# Main_PCB.net
KiCad netlist of a schematic drawn in Altium Designer
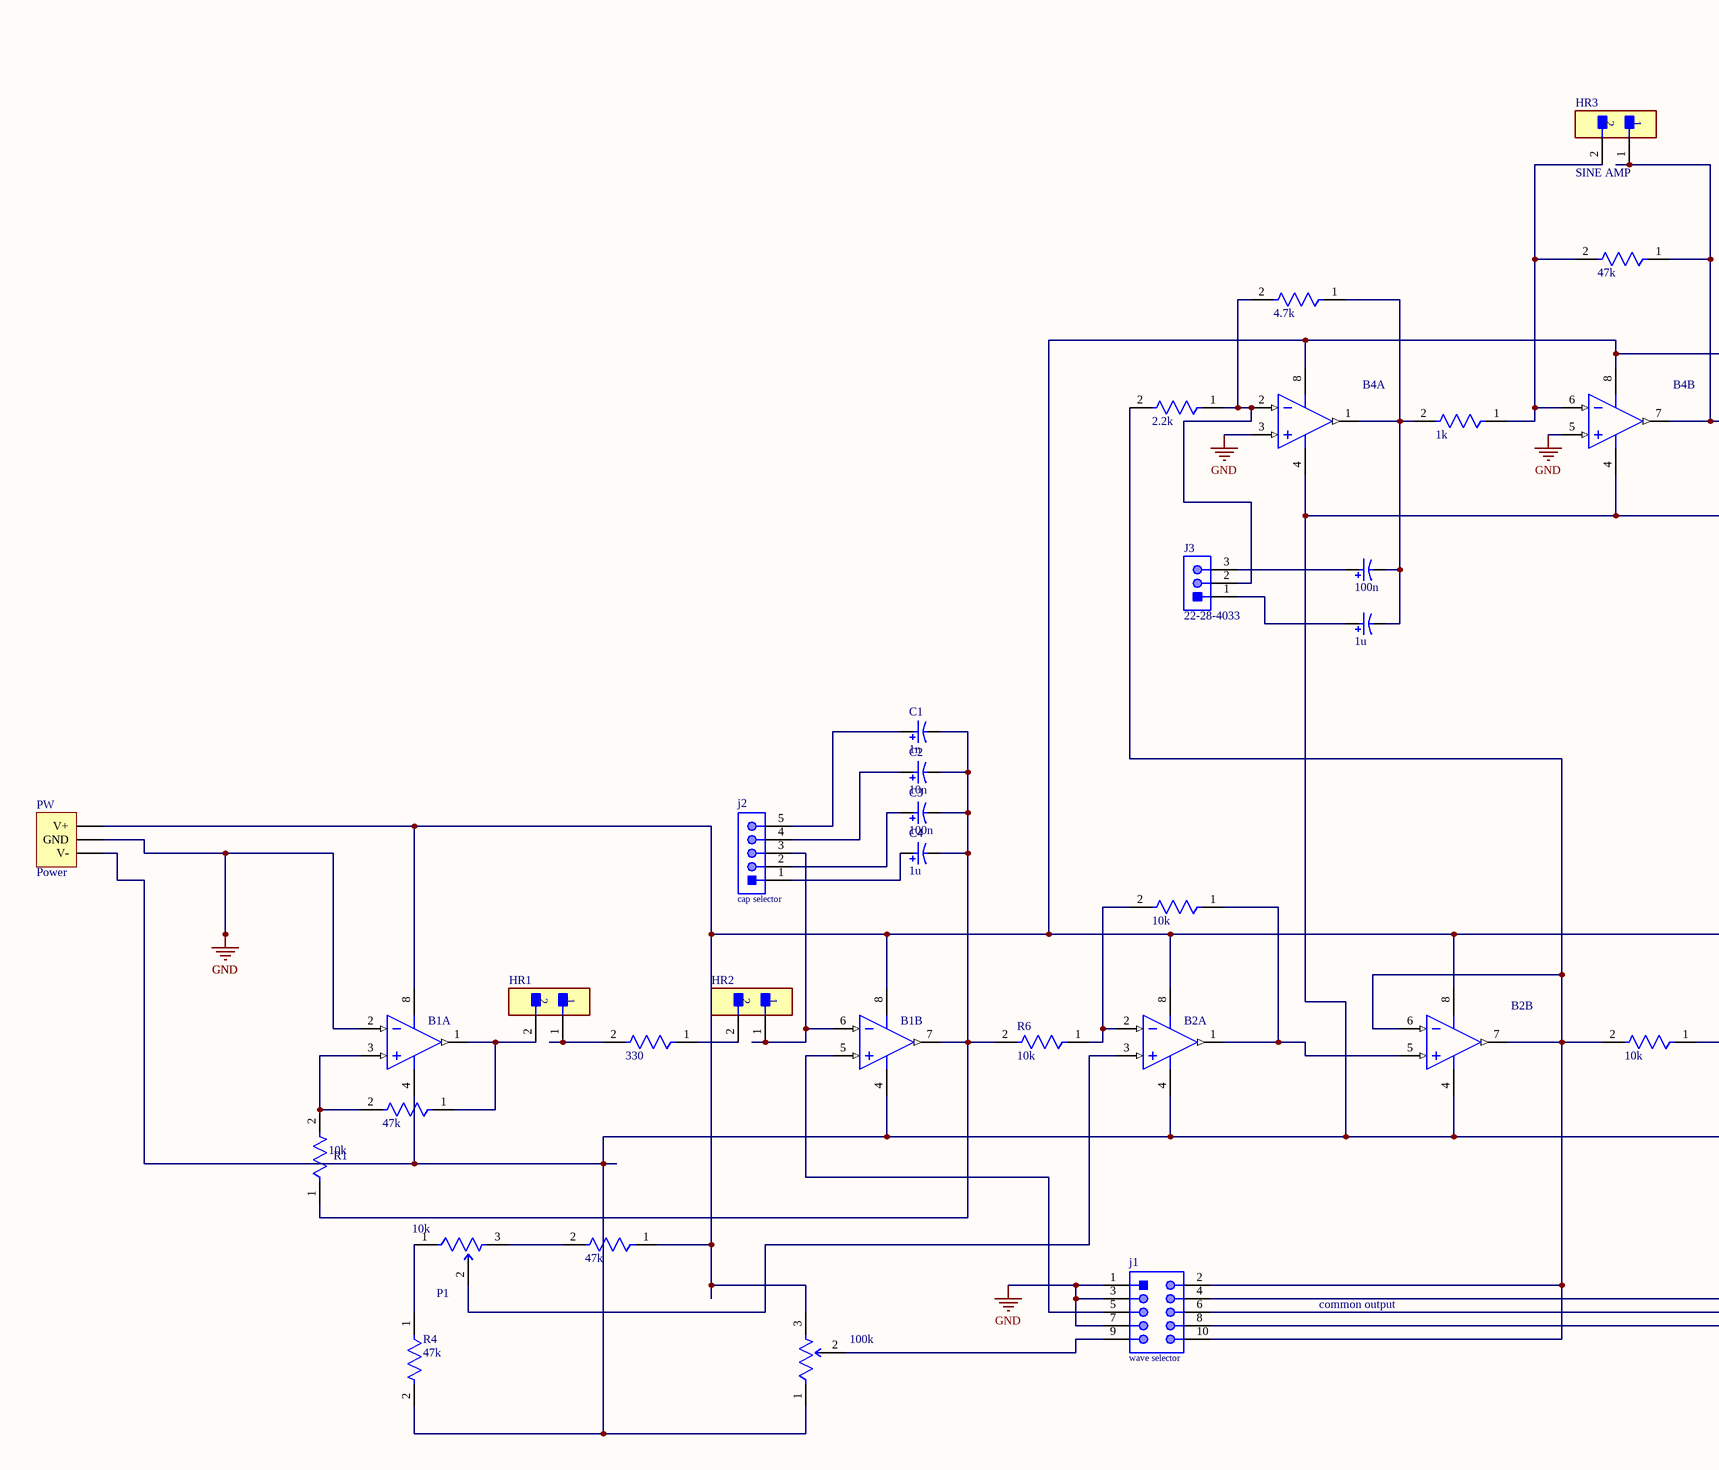
[diagram p0: Main_PCB.SchDoc, left]
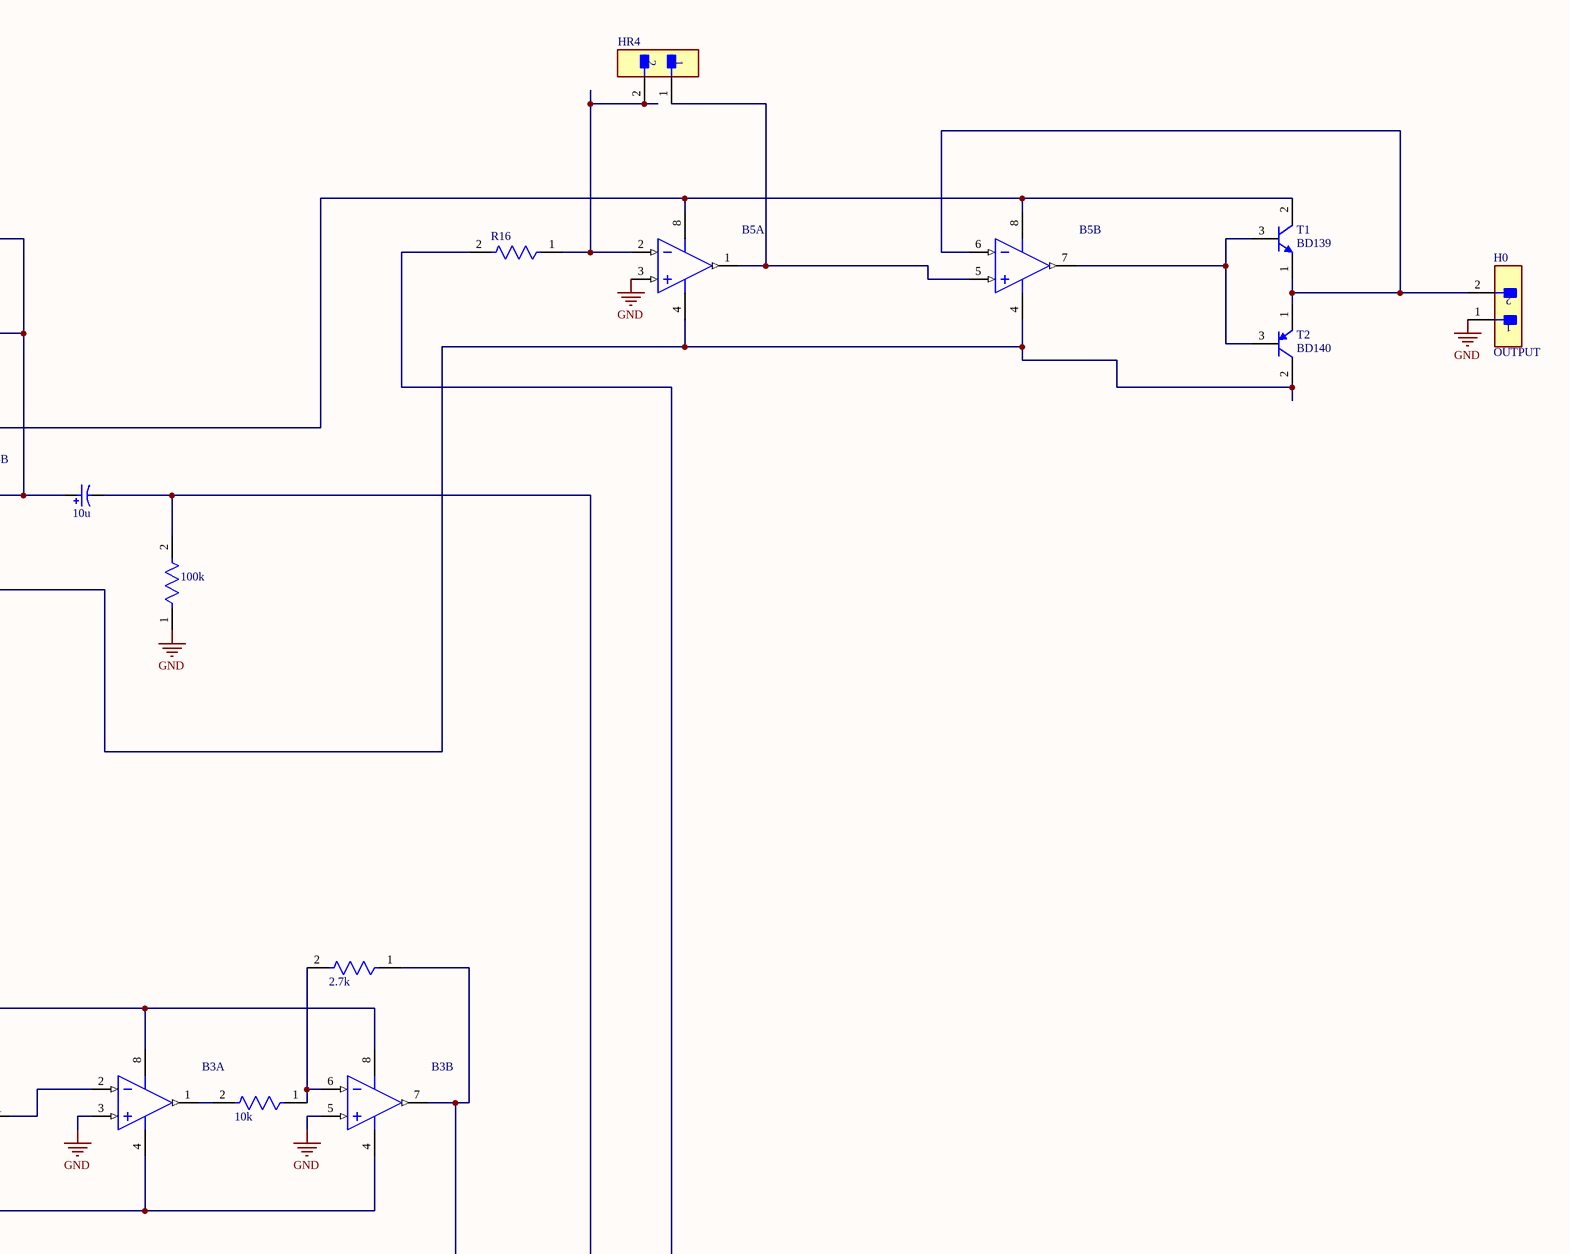
[diagram p1: Main_PCB.SchDoc, right]

(export (version "E")
  (design (tool "Eeschema 10.0.6"))
  (components
    (comp (ref "B1")
      (value "integrator")
      (footprint "ADI-N-8")
      (fields
        (field (name "MANUFACTURER") "Analog Devices")
        (field (name "PARTNUMBER") "AD826ANZ")
        (field (name "GENERIC PART NUMBER") "AD826")
      )
      (libsource (lib "Altium Content Vault") (part "ADI-AD7xx_8xx-X-8"))
    )
    (comp (ref "B2")
      (value "comparator gain")
      (footprint "ADI-N-8")
      (fields
        (field (name "MANUFACTURER") "Analog Devices")
        (field (name "PARTNUMBER") "AD826ANZ")
        (field (name "GENERIC PART NUMBER") "AD826")
      )
      (libsource (lib "Altium Content Vault") (part "ADI-AD7xx_8xx-X-8"))
    )
    (comp (ref "B3")
      (value "AD826ANZ")
      (footprint "ADI-N-8")
      (fields (field (name "MANUFACTURER") "Analog Devices") (field (name "GENERIC PART NUMBER") "AD826"))
      (libsource (lib "Altium Content Vault") (part "ADI-AD7xx_8xx-X-8"))
    )
    (comp (ref "B4")
      (value "AD826ANZ")
      (footprint "ADI-N-8")
      (fields (field (name "MANUFACTURER") "Analog Devices") (field (name "GENERIC PART NUMBER") "AD826"))
      (libsource (lib "Altium Content Vault") (part "ADI-AD7xx_8xx-X-8"))
    )
    (comp (ref "B5")
      (value "AD826ANZ")
      (footprint "ADI-N-8")
      (fields (field (name "MANUFACTURER") "Analog Devices") (field (name "GENERIC PART NUMBER") "AD826"))
      (libsource (lib "Altium Content Vault") (part "ADI-AD7xx_8xx-X-8"))
    )
    (comp (ref "C1")
      (value "1n")
      (footprint "CAPPR55-250-1120X630X1220")
      (fields (field (name "MANUFACTURER") "Panasonic"))
      (libsource (lib "Altium Content Vault") (part "CAP-P-2"))
    )
    (comp (ref "C2")
      (value "10n")
      (footprint "CAPPR55-250-1120X630X1220")
      (fields (field (name "MANUFACTURER") "Panasonic"))
      (libsource (lib "Altium Content Vault") (part "CAP-P-2"))
    )
    (comp (ref "C3")
      (value "100n")
      (footprint "CAPPR55-250-1120X630X1220")
      (fields (field (name "MANUFACTURER") "Panasonic"))
      (libsource (lib "Altium Content Vault") (part "CAP-P-2"))
    )
    (comp (ref "C4")
      (value "1u")
      (footprint "CAPPR55-250-1120X630X1220")
      (fields (field (name "MANUFACTURER") "Panasonic"))
      (libsource (lib "Altium Content Vault") (part "CAP-P-2"))
    )
    (comp (ref "C5")
      (value "100n")
      (footprint "CAPPR55-250-1120X630X1220")
      (fields (field (name "MANUFACTURER") "Panasonic"))
      (libsource (lib "Altium Content Vault") (part "CAP-P-2"))
    )
    (comp (ref "C6")
      (value "1u")
      (footprint "CAPPR55-250-1120X630X1220")
      (fields (field (name "MANUFACTURER") "Panasonic"))
      (libsource (lib "Altium Content Vault") (part "CAP-P-2"))
    )
    (comp (ref "C7")
      (value "10u")
      (footprint "CAPPR55-250-1120X630X1220")
      (fields (field (name "MANUFACTURER") "Panasonic"))
      (libsource (lib "Altium Content Vault") (part "CAP-P-2"))
    )
    (comp (ref "H0")
      (value "OUTPUT")
      (footprint "FP-TSW-102-07-L-S-MFG")
      (description "CONN HEADER VERT 2POS 2.54MM")
      (libsource (lib "") (part "3bc925449376181038e59eaffc5286c_1"))
    )
    (comp (ref "HR1")
      (value "FREQ")
      (footprint "FP-TSW-102-07-L-S-MFG")
      (description "CONN HEADER VERT 2POS 2.54MM")
      (libsource (lib "Altium Content Vault") (part "3bc925449376181038e59eaffc5286c"))
    )
    (comp (ref "HR2")
      (value "FREQ")
      (footprint "FP-TSW-102-07-L-S-MFG")
      (description "CONN HEADER VERT 2POS 2.54MM")
      (libsource (lib "Altium Content Vault") (part "3bc925449376181038e59eaffc5286c"))
    )
    (comp (ref "HR3")
      (value "SINE AMP")
      (footprint "FP-TSW-102-07-L-S-MFG")
      (description "CONN HEADER VERT 2POS 2.54MM")
      (libsource (lib "Altium Content Vault") (part "3bc925449376181038e59eaffc5286c"))
    )
    (comp (ref "HR4")
      (value "AMP")
      (footprint "FP-TSW-102-07-L-S-MFG")
      (description "CONN HEADER VERT 2POS 2.54MM")
      (libsource (lib "Altium Content Vault") (part "3bc925449376181038e59eaffc5286c"))
    )
    (comp (ref "j1")
      (value "wave selector")
      (footprint "61301021121")
      (description "THT Vertical Pin Header WR-PHD, Pitch 2.54 mm, Dual Row, 10 pins")
      (fields
        (field (name "MANUFACTURER") "Wurth Elektronik")
        (field (name "PART NUMBER") "61301021121")
        (field (name "PUBLISHER") "WurthElektronik")
      )
      (libsource (lib "Altium Content Vault") (part "WE-CN-2P-M-R10"))
    )
    (comp (ref "j2")
      (value "cap selector")
      (footprint "61300511121")
      (description "THT Vertical Pin Header WR-PHD, Pitch 2.54 mm, Single Row, 5 pins")
      (fields
        (field (name "PART NUMBER") "61300511121")
        (field (name "MANUFACTURER") "Wurth Elektronik")
        (field (name "PUBLISHER") "WurthElektronik")
      )
      (libsource (lib "Altium Content Vault") (part "WE-CN-1P-M-R5"))
    )
    (comp (ref "J3")
      (value "22-28-4033")
      (footprint "MOLX-22-28-4033_V")
      (description "Male Header, Pitch 2.54 mm, 1 x 3 Position, Height 8.38 mm, Tail Length 3.18 mm, RoHS, Bulk")
      (fields (field (name "MANUFACTURER") "Molex"))
      (libsource (lib "Altium Content Vault") (part "CN-1P-M-R3"))
    )
    (comp (ref "P1")
      (value "10k")
      (footprint "FP-3362P-1-503TLF-MFG")
      (description "TRIMMER 50K OHM 0.5W PC PIN TOP")
      (fields (field (name "TOLERANCE") "10%"))
      (libsource (lib "Altium Content Vault") (part "2dcfd2547301a7d3209a5e99acfd772"))
    )
    (comp (ref "P2")
      (value "100k")
      (footprint "FP-3362P-1-503TLF-MFG")
      (description "TRIMMER 50K OHM 0.5W PC PIN TOP")
      (fields (field (name "TOLERANCE") "10%"))
      (libsource (lib "Altium Content Vault") (part "2dcfd2547301a7d3209a5e99acfd772"))
    )
    (comp (ref "PW")
      (value "Power")
      (footprint "HDR1X3")
      (description "Header, 3-Pin")
      (fields (field (name "PUBLISHER") "Altium Limited"))
      (libsource (lib "Miscellaneous Connectors") (part "Header 3"))
    )
    (comp (ref "R1")
      (value "10k")
      (footprint "FP-CF18-MFG")
      (description "RES 10K OHM 1/8W 5% CF AXIAL")
      (fields
        (field (name "MANUFACTURER PART NUMBER") "CF18JT10K0")
        (field (name "MANUFACTURER") "Stackpole Electronics")
      )
      (libsource (lib "Altium Content Vault") (part "1029c3af85768c4190bb7ad29bc67b5"))
    )
    (comp (ref "R2")
      (value "47k")
      (footprint "FP-CF18-MFG")
      (description "RES 10K OHM 1/8W 5% CF AXIAL")
      (fields
        (field (name "MANUFACTURER PART NUMBER") "CF18JT10K0")
        (field (name "MANUFACTURER") "Stackpole Electronics")
      )
      (libsource (lib "Altium Content Vault") (part "1029c3af85768c4190bb7ad29bc67b5"))
    )
    (comp (ref "R3")
      (value "330")
      (footprint "FP-CF18-MFG")
      (description "RES 10K OHM 1/8W 5% CF AXIAL")
      (fields
        (field (name "MANUFACTURER PART NUMBER") "CF18JT10K0")
        (field (name "MANUFACTURER") "Stackpole Electronics")
      )
      (libsource (lib "Altium Content Vault") (part "1029c3af85768c4190bb7ad29bc67b5"))
    )
    (comp (ref "R4")
      (value "47k")
      (footprint "FP-CF18-MFG")
      (description "RES 10K OHM 1/8W 5% CF AXIAL")
      (fields
        (field (name "MANUFACTURER PART NUMBER") "CF18JT10K0")
        (field (name "MANUFACTURER") "Stackpole Electronics")
      )
      (libsource (lib "Altium Content Vault") (part "1029c3af85768c4190bb7ad29bc67b5"))
    )
    (comp (ref "R5")
      (value "47k")
      (footprint "FP-CF18-MFG")
      (description "RES 10K OHM 1/8W 5% CF AXIAL")
      (fields
        (field (name "MANUFACTURER PART NUMBER") "CF18JT10K0")
        (field (name "MANUFACTURER") "Stackpole Electronics")
      )
      (libsource (lib "Altium Content Vault") (part "1029c3af85768c4190bb7ad29bc67b5"))
    )
    (comp (ref "R6")
      (value "10k")
      (footprint "FP-CF18-MFG")
      (description "RES 10K OHM 1/8W 5% CF AXIAL")
      (fields
        (field (name "MANUFACTURER PART NUMBER") "CF18JT10K0")
        (field (name "MANUFACTURER") "Stackpole Electronics")
      )
      (libsource (lib "Altium Content Vault") (part "1029c3af85768c4190bb7ad29bc67b5"))
    )
    (comp (ref "R7")
      (value "10k")
      (footprint "FP-CF18-MFG")
      (description "RES 10K OHM 1/8W 5% CF AXIAL")
      (fields
        (field (name "MANUFACTURER PART NUMBER") "CF18JT10K0")
        (field (name "MANUFACTURER") "Stackpole Electronics")
      )
      (libsource (lib "Altium Content Vault") (part "1029c3af85768c4190bb7ad29bc67b5"))
    )
    (comp (ref "R8")
      (value "10k")
      (footprint "FP-CF18-MFG")
      (description "RES 10K OHM 1/8W 5% CF AXIAL")
      (fields
        (field (name "MANUFACTURER PART NUMBER") "CF18JT10K0")
        (field (name "MANUFACTURER") "Stackpole Electronics")
      )
      (libsource (lib "Altium Content Vault") (part "1029c3af85768c4190bb7ad29bc67b5"))
    )
    (comp (ref "R9")
      (value "10k")
      (footprint "FP-CF18-MFG")
      (description "RES 10K OHM 1/8W 5% CF AXIAL")
      (fields
        (field (name "MANUFACTURER PART NUMBER") "CF18JT10K0")
        (field (name "MANUFACTURER") "Stackpole Electronics")
      )
      (libsource (lib "Altium Content Vault") (part "1029c3af85768c4190bb7ad29bc67b5"))
    )
    (comp (ref "R10")
      (value "2.7k")
      (footprint "FP-CF18-MFG")
      (description "RES 10K OHM 1/8W 5% CF AXIAL")
      (fields
        (field (name "MANUFACTURER PART NUMBER") "CF18JT10K0")
        (field (name "MANUFACTURER") "Stackpole Electronics")
      )
      (libsource (lib "Altium Content Vault") (part "1029c3af85768c4190bb7ad29bc67b5"))
    )
    (comp (ref "R11")
      (value "2.2k")
      (footprint "FP-CF18-MFG")
      (description "RES 10K OHM 1/8W 5% CF AXIAL")
      (fields
        (field (name "MANUFACTURER PART NUMBER") "CF18JT10K0")
        (field (name "MANUFACTURER") "Stackpole Electronics")
      )
      (libsource (lib "Altium Content Vault") (part "1029c3af85768c4190bb7ad29bc67b5"))
    )
    (comp (ref "R12")
      (value "4.7k")
      (footprint "FP-CF18-MFG")
      (description "RES 10K OHM 1/8W 5% CF AXIAL")
      (fields
        (field (name "MANUFACTURER PART NUMBER") "CF18JT10K0")
        (field (name "MANUFACTURER") "Stackpole Electronics")
      )
      (libsource (lib "Altium Content Vault") (part "1029c3af85768c4190bb7ad29bc67b5"))
    )
    (comp (ref "R13")
      (value "1k")
      (footprint "FP-CF18-MFG")
      (description "RES 10K OHM 1/8W 5% CF AXIAL")
      (fields
        (field (name "MANUFACTURER PART NUMBER") "CF18JT10K0")
        (field (name "MANUFACTURER") "Stackpole Electronics")
      )
      (libsource (lib "Altium Content Vault") (part "1029c3af85768c4190bb7ad29bc67b5"))
    )
    (comp (ref "R14")
      (value "47k")
      (footprint "FP-CF18-MFG")
      (description "RES 10K OHM 1/8W 5% CF AXIAL")
      (fields
        (field (name "MANUFACTURER PART NUMBER") "CF18JT10K0")
        (field (name "MANUFACTURER") "Stackpole Electronics")
      )
      (libsource (lib "Altium Content Vault") (part "1029c3af85768c4190bb7ad29bc67b5"))
    )
    (comp (ref "R15")
      (value "100k")
      (footprint "FP-CF18-MFG")
      (description "RES 10K OHM 1/8W 5% CF AXIAL")
      (fields
        (field (name "MANUFACTURER PART NUMBER") "CF18JT10K0")
        (field (name "MANUFACTURER") "Stackpole Electronics")
      )
      (libsource (lib "Altium Content Vault") (part "1029c3af85768c4190bb7ad29bc67b5"))
    )
    (comp (ref "R16")
      (value "10k")
      (footprint "FP-CF18-MFG")
      (description "RES 10K OHM 1/8W 5% CF AXIAL")
      (fields
        (field (name "MANUFACTURER PART NUMBER") "CF18JT10K0")
        (field (name "MANUFACTURER") "Stackpole Electronics")
      )
      (libsource (lib "Altium Content Vault") (part "1029c3af85768c4190bb7ad29bc67b5"))
    )
    (comp (ref "T1")
      (value "BD139")
      (footprint "ONSC-TO-225-3-77-09")
      (description "Plastic Medium-Power Silicon NPN Transistor, 3-Pin TO-225, Bulk Box")
      (fields (field (name "MANUFACTURER") "On Semiconductor"))
      (libsource (lib "Altium Content Vault") (part "ONSC-NPN-E1C2B3-3"))
    )
    (comp (ref "T2")
      (value "BD140")
      (footprint "ONSC-TO-225-3-77-09")
      (description "Plastic Medium-Power Silicon PNP Transistor, 3-Pin TO-225, Bulk Box")
      (fields (field (name "MANUFACTURER") "On Semiconductor"))
      (libsource (lib "Altium Content Vault") (part "ONSC-PNP-E1C2B3-3"))
    )
  )
  (nets
    (net (code "1") (name "GND") (class "Default")
      (node (ref "B1") (pin "2") (pinfunction "-IN_1_2") (pintype "input"))
      (node (ref "B3") (pin "3") (pinfunction "+IN_1_3") (pintype "input"))
      (node (ref "B3") (pin "5") (pinfunction "+IN_2_5") (pintype "input"))
      (node (ref "B4") (pin "3") (pinfunction "+IN_1_3") (pintype "input"))
      (node (ref "B4") (pin "5") (pinfunction "+IN_2_5") (pintype "input"))
      (node (ref "B5") (pin "3") (pinfunction "+IN_1_3") (pintype "input"))
      (node (ref "H0") (pin "1") (pinfunction "1_1") (pintype "passive"))
      (node (ref "PW") (pin "2") (pinfunction "GND_2") (pintype "passive"))
      (node (ref "R15") (pin "1") (pinfunction "1_1") (pintype "passive"))
      (node (ref "j1") (pin "1") (pinfunction "1_1") (pintype "passive"))
      (node (ref "j1") (pin "3") (pinfunction "3_3") (pintype "passive"))
      (node (ref "j1") (pin "7") (pinfunction "7_7") (pintype "passive"))
    )
    (net (code "2") (name "Net-(B1A-+IN_1)") (class "Default")
      (node (ref "B1") (pin "3") (pinfunction "+IN_1_3") (pintype "input"))
      (node (ref "R1") (pin "2") (pinfunction "2_2") (pintype "passive"))
      (node (ref "R2") (pin "2") (pinfunction "2_2") (pintype "passive"))
    )
    (net (code "3") (name "Net-(B1A-+V)") (class "Default")
      (node (ref "B1") (pin "8") (pinfunction "+V_8") (pintype "power_in"))
      (node (ref "B2") (pin "8") (pinfunction "+V_8") (pintype "power_in"))
      (node (ref "B3") (pin "8") (pinfunction "+V_8") (pintype "power_in"))
      (node (ref "B4") (pin "8") (pinfunction "+V_8") (pintype "power_in"))
      (node (ref "B5") (pin "8") (pinfunction "+V_8") (pintype "power_in"))
      (node (ref "P2") (pin "3") (pinfunction "CW_3") (pintype "passive"))
      (node (ref "PW") (pin "1") (pinfunction "V+_1") (pintype "passive"))
      (node (ref "R5") (pin "1") (pinfunction "1_1") (pintype "passive"))
      (node (ref "T1") (pin "2") (pinfunction "C_2") (pintype "passive"))
    )
    (net (code "4") (name "Net-(B1A--V)") (class "Default")
      (node (ref "B1") (pin "4") (pinfunction "-V_4") (pintype "power_in"))
      (node (ref "B2") (pin "4") (pinfunction "-V_4") (pintype "power_in"))
      (node (ref "B3") (pin "4") (pinfunction "-V_4") (pintype "power_in"))
      (node (ref "B4") (pin "4") (pinfunction "-V_4") (pintype "power_in"))
      (node (ref "B5") (pin "4") (pinfunction "-V_4") (pintype "power_in"))
      (node (ref "P2") (pin "1") (pinfunction "CCW_1") (pintype "passive"))
      (node (ref "PW") (pin "3") (pinfunction "V-_3") (pintype "passive"))
      (node (ref "R4") (pin "2") (pinfunction "2_2") (pintype "passive"))
      (node (ref "T2") (pin "2") (pinfunction "C_2") (pintype "passive"))
    )
    (net (code "5") (name "Net-(B1A-OUT_1)") (class "Default")
      (node (ref "B1") (pin "1") (pinfunction "OUT_1_1") (pintype "output"))
      (node (ref "HR1") (pin "2") (pinfunction "2_2") (pintype "passive"))
      (node (ref "R2") (pin "1") (pinfunction "1_1") (pintype "passive"))
    )
    (net (code "6") (name "Net-(B1B-+IN_2)") (class "Default")
      (node (ref "B1") (pin "5") (pinfunction "+IN_2_5") (pintype "input"))
      (node (ref "j1") (pin "5") (pinfunction "5_5") (pintype "passive"))
    )
    (net (code "7") (name "Net-(B1B--IN_2)") (class "Default")
      (node (ref "B1") (pin "6") (pinfunction "-IN_2_6") (pintype "input"))
      (node (ref "HR2") (pin "1") (pinfunction "1_1") (pintype "passive"))
      (node (ref "j2") (pin "3") (pinfunction "3_3") (pintype "passive"))
    )
    (net (code "8") (name "Net-(B1B-OUT_2)") (class "Default")
      (node (ref "B1") (pin "7") (pinfunction "OUT_2_7") (pintype "output"))
      (node (ref "C1") (pin "2") (pinfunction "2_2") (pintype "passive"))
      (node (ref "C2") (pin "2") (pinfunction "2_2") (pintype "passive"))
      (node (ref "C3") (pin "2") (pinfunction "2_2") (pintype "passive"))
      (node (ref "C4") (pin "2") (pinfunction "2_2") (pintype "passive"))
      (node (ref "R1") (pin "1") (pinfunction "1_1") (pintype "passive"))
      (node (ref "R6") (pin "2") (pinfunction "2_2") (pintype "passive"))
    )
    (net (code "9") (name "Net-(B2A-+IN_1)") (class "Default")
      (node (ref "B2") (pin "3") (pinfunction "+IN_1_3") (pintype "input"))
      (node (ref "P1") (pin "2") (pinfunction "WIPER_2") (pintype "passive"))
    )
    (net (code "10") (name "Net-(B2A--IN_1)") (class "Default")
      (node (ref "B2") (pin "2") (pinfunction "-IN_1_2") (pintype "input"))
      (node (ref "R6") (pin "1") (pinfunction "1_1") (pintype "passive"))
      (node (ref "R7") (pin "2") (pinfunction "2_2") (pintype "passive"))
    )
    (net (code "11") (name "Net-(B2A-OUT_1)") (class "Default")
      (node (ref "B2") (pin "1") (pinfunction "OUT_1_1") (pintype "output"))
      (node (ref "B2") (pin "5") (pinfunction "+IN_2_5") (pintype "input"))
      (node (ref "R7") (pin "1") (pinfunction "1_1") (pintype "passive"))
    )
    (net (code "12") (name "Net-(B2B--IN_2)") (class "Default")
      (node (ref "B2") (pin "6") (pinfunction "-IN_2_6") (pintype "input"))
      (node (ref "B2") (pin "7") (pinfunction "OUT_2_7") (pintype "output"))
      (node (ref "R11") (pin "2") (pinfunction "2_2") (pintype "passive"))
      (node (ref "R8") (pin "2") (pinfunction "2_2") (pintype "passive"))
      (node (ref "j1") (pin "10") (pinfunction "10_10") (pintype "passive"))
      (node (ref "j1") (pin "2") (pinfunction "2_2") (pintype "passive"))
    )
    (net (code "13") (name "Net-(B3A--IN_1)") (class "Default")
      (node (ref "B3") (pin "2") (pinfunction "-IN_1_2") (pintype "input"))
      (node (ref "R8") (pin "1") (pinfunction "1_1") (pintype "passive"))
    )
    (net (code "14") (name "Net-(B3A-OUT_1)") (class "Default")
      (node (ref "B3") (pin "1") (pinfunction "OUT_1_1") (pintype "output"))
      (node (ref "R9") (pin "2") (pinfunction "2_2") (pintype "passive"))
    )
    (net (code "15") (name "Net-(B3B--IN_2)") (class "Default")
      (node (ref "B3") (pin "6") (pinfunction "-IN_2_6") (pintype "input"))
      (node (ref "R10") (pin "2") (pinfunction "2_2") (pintype "passive"))
      (node (ref "R9") (pin "1") (pinfunction "1_1") (pintype "passive"))
    )
    (net (code "16") (name "Net-(B3B-OUT_2)") (class "Default")
      (node (ref "B3") (pin "7") (pinfunction "OUT_2_7") (pintype "output"))
      (node (ref "R10") (pin "1") (pinfunction "1_1") (pintype "passive"))
      (node (ref "j1") (pin "4") (pinfunction "4_4") (pintype "passive"))
    )
    (net (code "17") (name "Net-(B4A--IN_1)") (class "Default")
      (node (ref "B4") (pin "2") (pinfunction "-IN_1_2") (pintype "input"))
      (node (ref "J3") (pin "2") (pinfunction "2_2") (pintype "passive"))
      (node (ref "R11") (pin "1") (pinfunction "1_1") (pintype "passive"))
      (node (ref "R12") (pin "2") (pinfunction "2_2") (pintype "passive"))
    )
    (net (code "18") (name "Net-(B4A-OUT_1)") (class "Default")
      (node (ref "B4") (pin "1") (pinfunction "OUT_1_1") (pintype "output"))
      (node (ref "C5") (pin "2") (pinfunction "2_2") (pintype "passive"))
      (node (ref "C6") (pin "2") (pinfunction "2_2") (pintype "passive"))
      (node (ref "R12") (pin "1") (pinfunction "1_1") (pintype "passive"))
      (node (ref "R13") (pin "2") (pinfunction "2_2") (pintype "passive"))
    )
    (net (code "19") (name "Net-(B4B--IN_2)") (class "Default")
      (node (ref "B4") (pin "6") (pinfunction "-IN_2_6") (pintype "input"))
      (node (ref "HR3") (pin "2") (pinfunction "2_2") (pintype "passive"))
      (node (ref "R13") (pin "1") (pinfunction "1_1") (pintype "passive"))
      (node (ref "R14") (pin "2") (pinfunction "2_2") (pintype "passive"))
    )
    (net (code "20") (name "Net-(B4B-OUT_2)") (class "Default")
      (node (ref "B4") (pin "7") (pinfunction "OUT_2_7") (pintype "output"))
      (node (ref "C7") (pin "1") (pinfunction "1_1") (pintype "passive"))
      (node (ref "HR3") (pin "1") (pinfunction "1_1") (pintype "passive"))
      (node (ref "R14") (pin "1") (pinfunction "1_1") (pintype "passive"))
    )
    (net (code "21") (name "Net-(B5A--IN_1)") (class "Default")
      (node (ref "B5") (pin "2") (pinfunction "-IN_1_2") (pintype "input"))
      (node (ref "HR4") (pin "2") (pinfunction "2_2") (pintype "passive"))
      (node (ref "R16") (pin "1") (pinfunction "1_1") (pintype "passive"))
    )
    (net (code "22") (name "Net-(B5A-OUT_1)") (class "Default")
      (node (ref "B5") (pin "1") (pinfunction "OUT_1_1") (pintype "output"))
      (node (ref "B5") (pin "5") (pinfunction "+IN_2_5") (pintype "input"))
      (node (ref "HR4") (pin "1") (pinfunction "1_1") (pintype "passive"))
    )
    (net (code "23") (name "Net-(B5B--IN_2)") (class "Default")
      (node (ref "B5") (pin "6") (pinfunction "-IN_2_6") (pintype "input"))
      (node (ref "H0") (pin "2") (pinfunction "2_2") (pintype "passive"))
      (node (ref "T1") (pin "1") (pinfunction "E_1") (pintype "passive"))
      (node (ref "T2") (pin "1") (pinfunction "E_1") (pintype "passive"))
    )
    (net (code "24") (name "Net-(B5B-OUT_2)") (class "Default")
      (node (ref "B5") (pin "7") (pinfunction "OUT_2_7") (pintype "output"))
      (node (ref "T1") (pin "3") (pinfunction "B_3") (pintype "passive"))
      (node (ref "T2") (pin "3") (pinfunction "B_3") (pintype "passive"))
    )
    (net (code "25") (name "Net-(C1-Pad1)") (class "Default")
      (node (ref "C1") (pin "1") (pinfunction "1_1") (pintype "passive"))
      (node (ref "j2") (pin "5") (pinfunction "5_5") (pintype "passive"))
    )
    (net (code "26") (name "Net-(C2-Pad1)") (class "Default")
      (node (ref "C2") (pin "1") (pinfunction "1_1") (pintype "passive"))
      (node (ref "j2") (pin "4") (pinfunction "4_4") (pintype "passive"))
    )
    (net (code "27") (name "Net-(C3-Pad1)") (class "Default")
      (node (ref "C3") (pin "1") (pinfunction "1_1") (pintype "passive"))
      (node (ref "j2") (pin "2") (pinfunction "2_2") (pintype "passive"))
    )
    (net (code "28") (name "Net-(C4-Pad1)") (class "Default")
      (node (ref "C4") (pin "1") (pinfunction "1_1") (pintype "passive"))
      (node (ref "j2") (pin "1") (pinfunction "1_1") (pintype "passive"))
    )
    (net (code "29") (name "Net-(C5-Pad1)") (class "Default")
      (node (ref "C5") (pin "1") (pinfunction "1_1") (pintype "passive"))
      (node (ref "J3") (pin "3") (pinfunction "3_3") (pintype "passive"))
    )
    (net (code "30") (name "Net-(C6-Pad1)") (class "Default")
      (node (ref "C6") (pin "1") (pinfunction "1_1") (pintype "passive"))
      (node (ref "J3") (pin "1") (pinfunction "1_1") (pintype "passive"))
    )
    (net (code "31") (name "Net-(C7-Pad2)") (class "Default")
      (node (ref "C7") (pin "2") (pinfunction "2_2") (pintype "passive"))
      (node (ref "R15") (pin "2") (pinfunction "2_2") (pintype "passive"))
      (node (ref "j1") (pin "8") (pinfunction "8_8") (pintype "passive"))
    )
    (net (code "32") (name "Net-(HR1-Pad1)") (class "Default")
      (node (ref "HR1") (pin "1") (pinfunction "1_1") (pintype "passive"))
      (node (ref "R3") (pin "2") (pinfunction "2_2") (pintype "passive"))
    )
    (net (code "33") (name "Net-(HR2-Pad2)") (class "Default")
      (node (ref "HR2") (pin "2") (pinfunction "2_2") (pintype "passive"))
      (node (ref "R3") (pin "1") (pinfunction "1_1") (pintype "passive"))
    )
    (net (code "34") (name "Net-(P1-CCW)") (class "Default")
      (node (ref "P1") (pin "1") (pinfunction "CCW_1") (pintype "passive"))
      (node (ref "R4") (pin "1") (pinfunction "1_1") (pintype "passive"))
    )
    (net (code "35") (name "Net-(P1-CW)") (class "Default")
      (node (ref "P1") (pin "3") (pinfunction "CW_3") (pintype "passive"))
      (node (ref "R5") (pin "2") (pinfunction "2_2") (pintype "passive"))
    )
    (net (code "36") (name "Net-(P2-WIPER)") (class "Default")
      (node (ref "P2") (pin "2") (pinfunction "WIPER_2") (pintype "passive"))
      (node (ref "j1") (pin "9") (pinfunction "9_9") (pintype "passive"))
    )
    (net (code "37") (name "Net-(R16-Pad2)") (class "Default")
      (node (ref "R16") (pin "2") (pinfunction "2_2") (pintype "passive"))
      (node (ref "j1") (pin "6") (pinfunction "6_6") (pintype "passive"))
    )
  )
)
